# QCopterFC_MCU_Sch.net
KiCad netlist of a schematic drawn in Altium Designer
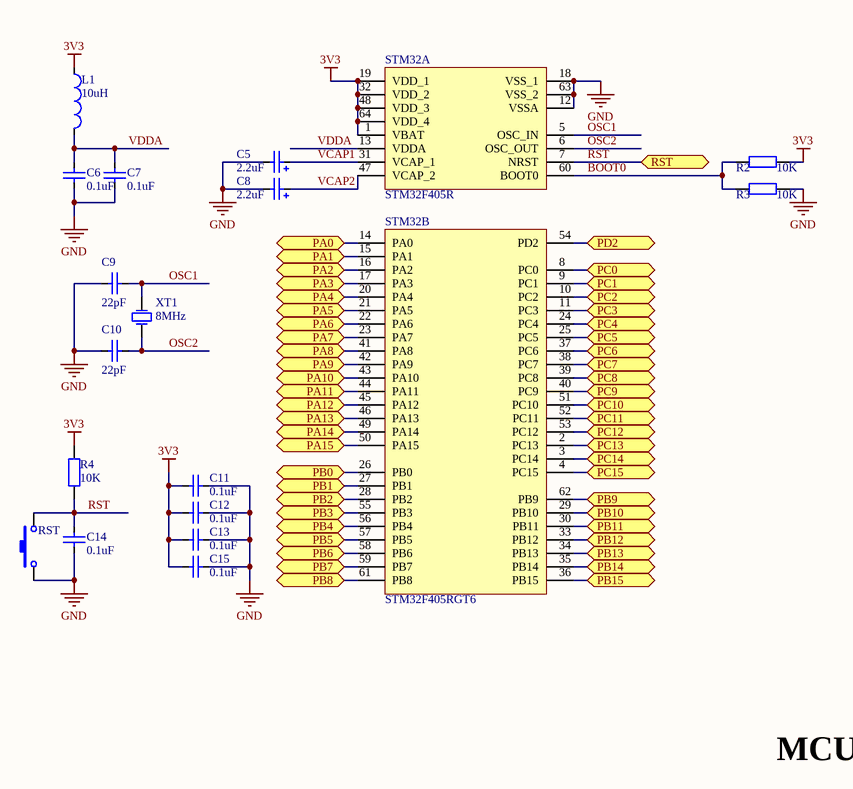
[diagram p0: QCopterFC_MCU_Sch.SchDoc]

(export (version "E")
  (design (tool "Eeschema 10.0.6"))
  (components
    (comp (ref "C5")
      (value "2.2uF")
      (footprint "PCB_Passive:CAP_TAN_P0805")
      (description "Capacitor")
      (fields (field (name "Comment") "Cap_Tan_0805"))
      (libsource (lib "SCH_Passive") (part "Cap_Tan_0805"))
    )
    (comp (ref "C6")
      (value "0.1uF")
      (footprint "PCB_Passive:CAP_0603")
      (description "Capacitor")
      (fields (field (name "Comment") "Cap_0603"))
      (libsource (lib "SCH_Passive") (part "Cap_0603"))
    )
    (comp (ref "C7")
      (value "0.1uF")
      (footprint "PCB_Passive:CAP_0603")
      (description "Capacitor")
      (fields (field (name "Comment") "Cap_0603"))
      (libsource (lib "SCH_Passive") (part "Cap_0603"))
    )
    (comp (ref "C8")
      (value "2.2uF")
      (footprint "PCB_Passive:CAP_TAN_P0805")
      (description "Capacitor")
      (fields (field (name "Comment") "Cap_Tan_0805"))
      (libsource (lib "SCH_Passive") (part "Cap_Tan_0805"))
    )
    (comp (ref "C9")
      (value "22pF")
      (footprint "PCB_Passive:CAP_0603")
      (description "Capacitor")
      (fields (field (name "Comment") "Cap_0603"))
      (libsource (lib "SCH_Passive") (part "Cap_0603"))
    )
    (comp (ref "C10")
      (value "22pF")
      (footprint "PCB_Passive:CAP_0603")
      (description "Capacitor")
      (fields (field (name "Comment") "Cap_0603"))
      (libsource (lib "SCH_Passive") (part "Cap_0603"))
    )
    (comp (ref "C11")
      (value "0.1uF")
      (footprint "PCB_Passive:CAP_0603")
      (description "Capacitor")
      (fields (field (name "Comment") "Cap_0603"))
      (libsource (lib "SCH_Passive") (part "Cap_0603"))
    )
    (comp (ref "C12")
      (value "0.1uF")
      (footprint "PCB_Passive:CAP_0603")
      (description "Capacitor")
      (fields (field (name "Comment") "Cap_0603"))
      (libsource (lib "SCH_Passive") (part "Cap_0603"))
    )
    (comp (ref "C13")
      (value "0.1uF")
      (footprint "PCB_Passive:CAP_0603")
      (description "Capacitor")
      (fields (field (name "Comment") "Cap_0603"))
      (libsource (lib "SCH_Passive") (part "Cap_0603"))
    )
    (comp (ref "C14")
      (value "0.1uF")
      (footprint "PCB_Passive:CAP_0603")
      (description "Capacitor")
      (fields (field (name "Comment") "Cap_0603"))
      (libsource (lib "SCH_Passive") (part "Cap_0603"))
    )
    (comp (ref "C15")
      (value "0.1uF")
      (footprint "PCB_Passive:CAP_0603")
      (description "Capacitor")
      (fields (field (name "Comment") "Cap_0603"))
      (libsource (lib "SCH_Passive") (part "Cap_0603"))
    )
    (comp (ref "L1")
      (value "10uH")
      (footprint "PCB_Passive:IND_0603")
      (description "Inductor")
      (fields (field (name "Comment") "Ind_0603"))
      (libsource (lib "SCH_Passive") (part "Ind_0603"))
    )
    (comp (ref "R2")
      (value "10K")
      (footprint "PCB_Passive:RES_0603")
      (description "Resistor")
      (fields (field (name "Comment") "Res_0603"))
      (libsource (lib "SCH_Passive") (part "Res_0603"))
    )
    (comp (ref "R3")
      (value "10K")
      (footprint "PCB_Passive:RES_0603")
      (description "Resistor")
      (fields (field (name "Comment") "Res_0603"))
      (libsource (lib "SCH_Passive") (part "Res_0603"))
    )
    (comp (ref "R4")
      (value "10K")
      (footprint "PCB_Passive:RES_0603")
      (description "Resistor")
      (fields (field (name "Comment") "Res_0603"))
      (libsource (lib "") (part "Res_0603_1"))
    )
    (comp (ref "RST")
      (value "SW-PB_1")
      (footprint "PCB_Switch:BT_90_T")
      (description "Switch")
      (fields (field (name "PUBLISHER") "Altium Limited"))
      (libsource (lib "SCH_Switch") (part "SW-PB_1"))
    )
    (comp (ref "STM32")
      (value "STM32F405R")
      (footprint "PCB_IC:STM32F_64")
      (description "MCU")
      (libsource (lib "") (part "STM32F405R_1"))
    )
    (comp (ref "XT1")
      (value "8MHz")
      (footprint "PCB_Oscillator:XTAL_5032")
      (description "Crystal Oscillator")
      (fields (field (name "Comment") "XTAL_5032") (field (name "PUBLISHER") "Altium Limited"))
      (libsource (lib "SCH_Oscillator") (part "XTAL_5032"))
    )
  )
  (nets
    (net (code "1") (name "/BOOT0") (class "Default")
      (node (ref "R2") (pin "1") (pinfunction "1_1") (pintype "passive"))
      (node (ref "R3") (pin "1") (pinfunction "1_1") (pintype "passive"))
      (node (ref "STM32") (pin "60") (pinfunction "BOOT0_60") (pintype "passive"))
    )
    (net (code "2") (name "/OSC1") (class "Default")
      (node (ref "C9") (pin "2") (pinfunction "2_2") (pintype "passive"))
      (node (ref "STM32") (pin "5") (pinfunction "OSC_IN_5") (pintype "passive"))
      (node (ref "XT1") (pin "2") (pinfunction "OSC2_2") (pintype "passive"))
    )
    (net (code "3") (name "/OSC2") (class "Default")
      (node (ref "C10") (pin "2") (pinfunction "2_2") (pintype "passive"))
      (node (ref "STM32") (pin "6") (pinfunction "OSC_OUT_6") (pintype "passive"))
      (node (ref "XT1") (pin "1") (pinfunction "OSC1_1") (pintype "passive"))
    )
    (net (code "4") (name "/PA0") (class "Default")
      (node (ref "STM32") (pin "14") (pinfunction "PA0_14") (pintype "passive"))
    )
    (net (code "5") (name "/PA1") (class "Default")
      (node (ref "STM32") (pin "15") (pinfunction "PA1_15") (pintype "passive"))
    )
    (net (code "6") (name "/PA2") (class "Default")
      (node (ref "STM32") (pin "16") (pinfunction "PA2_16") (pintype "passive"))
    )
    (net (code "7") (name "/PA3") (class "Default")
      (node (ref "STM32") (pin "17") (pinfunction "PA3_17") (pintype "passive"))
    )
    (net (code "8") (name "/PA4") (class "Default")
      (node (ref "STM32") (pin "20") (pinfunction "PA4_20") (pintype "passive"))
    )
    (net (code "9") (name "/PA5") (class "Default")
      (node (ref "STM32") (pin "21") (pinfunction "PA5_21") (pintype "passive"))
    )
    (net (code "10") (name "/PA6") (class "Default")
      (node (ref "STM32") (pin "22") (pinfunction "PA6_22") (pintype "passive"))
    )
    (net (code "11") (name "/PA7") (class "Default")
      (node (ref "STM32") (pin "23") (pinfunction "PA7_23") (pintype "passive"))
    )
    (net (code "12") (name "/PA8") (class "Default")
      (node (ref "STM32") (pin "41") (pinfunction "PA8_41") (pintype "passive"))
    )
    (net (code "13") (name "/PA9") (class "Default")
      (node (ref "STM32") (pin "42") (pinfunction "PA9_42") (pintype "passive"))
    )
    (net (code "14") (name "/PA10") (class "Default")
      (node (ref "STM32") (pin "43") (pinfunction "PA10_43") (pintype "passive"))
    )
    (net (code "15") (name "/PA11") (class "Default")
      (node (ref "STM32") (pin "44") (pinfunction "PA11_44") (pintype "passive"))
    )
    (net (code "16") (name "/PA12") (class "Default")
      (node (ref "STM32") (pin "45") (pinfunction "PA12_45") (pintype "passive"))
    )
    (net (code "17") (name "/PA13") (class "Default")
      (node (ref "STM32") (pin "46") (pinfunction "PA13_46") (pintype "passive"))
    )
    (net (code "18") (name "/PA14") (class "Default")
      (node (ref "STM32") (pin "49") (pinfunction "PA14_49") (pintype "passive"))
    )
    (net (code "19") (name "/PA15") (class "Default")
      (node (ref "STM32") (pin "50") (pinfunction "PA15_50") (pintype "passive"))
    )
    (net (code "20") (name "/PB0") (class "Default")
      (node (ref "STM32") (pin "26") (pinfunction "PB0_26") (pintype "passive"))
    )
    (net (code "21") (name "/PB1") (class "Default")
      (node (ref "STM32") (pin "27") (pinfunction "PB1_27") (pintype "passive"))
    )
    (net (code "22") (name "/PB2") (class "Default")
      (node (ref "STM32") (pin "28") (pinfunction "PB2_28") (pintype "passive"))
    )
    (net (code "23") (name "/PB3") (class "Default")
      (node (ref "STM32") (pin "55") (pinfunction "PB3_55") (pintype "passive"))
    )
    (net (code "24") (name "/PB4") (class "Default")
      (node (ref "STM32") (pin "56") (pinfunction "PB4_56") (pintype "passive"))
    )
    (net (code "25") (name "/PB5") (class "Default")
      (node (ref "STM32") (pin "57") (pinfunction "PB5_57") (pintype "passive"))
    )
    (net (code "26") (name "/PB6") (class "Default")
      (node (ref "STM32") (pin "58") (pinfunction "PB6_58") (pintype "passive"))
    )
    (net (code "27") (name "/PB7") (class "Default")
      (node (ref "STM32") (pin "59") (pinfunction "PB7_59") (pintype "passive"))
    )
    (net (code "28") (name "/PB8") (class "Default")
      (node (ref "STM32") (pin "61") (pinfunction "PB8_61") (pintype "passive"))
    )
    (net (code "29") (name "/PB9") (class "Default")
      (node (ref "STM32") (pin "62") (pinfunction "PB9_62") (pintype "passive"))
    )
    (net (code "30") (name "/PB10") (class "Default")
      (node (ref "STM32") (pin "29") (pinfunction "PB10_29") (pintype "passive"))
    )
    (net (code "31") (name "/PB11") (class "Default")
      (node (ref "STM32") (pin "30") (pinfunction "PB11_30") (pintype "passive"))
    )
    (net (code "32") (name "/PB12") (class "Default")
      (node (ref "STM32") (pin "33") (pinfunction "PB12_33") (pintype "passive"))
    )
    (net (code "33") (name "/PB13") (class "Default")
      (node (ref "STM32") (pin "34") (pinfunction "PB13_34") (pintype "passive"))
    )
    (net (code "34") (name "/PB14") (class "Default")
      (node (ref "STM32") (pin "35") (pinfunction "PB14_35") (pintype "passive"))
    )
    (net (code "35") (name "/PB15") (class "Default")
      (node (ref "STM32") (pin "36") (pinfunction "PB15_36") (pintype "passive"))
    )
    (net (code "36") (name "/PC0") (class "Default")
      (node (ref "STM32") (pin "8") (pinfunction "PC0_8") (pintype "passive"))
    )
    (net (code "37") (name "/PC1") (class "Default")
      (node (ref "STM32") (pin "9") (pinfunction "PC1_9") (pintype "passive"))
    )
    (net (code "38") (name "/PC2") (class "Default")
      (node (ref "STM32") (pin "10") (pinfunction "PC2_10") (pintype "passive"))
    )
    (net (code "39") (name "/PC3") (class "Default")
      (node (ref "STM32") (pin "11") (pinfunction "PC3_11") (pintype "passive"))
    )
    (net (code "40") (name "/PC4") (class "Default")
      (node (ref "STM32") (pin "24") (pinfunction "PC4_24") (pintype "passive"))
    )
    (net (code "41") (name "/PC5") (class "Default")
      (node (ref "STM32") (pin "25") (pinfunction "PC5_25") (pintype "passive"))
    )
    (net (code "42") (name "/PC6") (class "Default")
      (node (ref "STM32") (pin "37") (pinfunction "PC6_37") (pintype "passive"))
    )
    (net (code "43") (name "/PC7") (class "Default")
      (node (ref "STM32") (pin "38") (pinfunction "PC7_38") (pintype "passive"))
    )
    (net (code "44") (name "/PC8") (class "Default")
      (node (ref "STM32") (pin "39") (pinfunction "PC8_39") (pintype "passive"))
    )
    (net (code "45") (name "/PC9") (class "Default")
      (node (ref "STM32") (pin "40") (pinfunction "PC9_40") (pintype "passive"))
    )
    (net (code "46") (name "/PC10") (class "Default")
      (node (ref "STM32") (pin "51") (pinfunction "PC10_51") (pintype "passive"))
    )
    (net (code "47") (name "/PC11") (class "Default")
      (node (ref "STM32") (pin "52") (pinfunction "PC11_52") (pintype "passive"))
    )
    (net (code "48") (name "/PC12") (class "Default")
      (node (ref "STM32") (pin "53") (pinfunction "PC12_53") (pintype "passive"))
    )
    (net (code "49") (name "/PC13") (class "Default")
      (node (ref "STM32") (pin "2") (pinfunction "PC13_2") (pintype "passive"))
    )
    (net (code "50") (name "/PC14") (class "Default")
      (node (ref "STM32") (pin "3") (pinfunction "PC14_3") (pintype "passive"))
    )
    (net (code "51") (name "/PC15") (class "Default")
      (node (ref "STM32") (pin "4") (pinfunction "PC15_4") (pintype "passive"))
    )
    (net (code "52") (name "/PD2") (class "Default")
      (node (ref "STM32") (pin "54") (pinfunction "PD2_54") (pintype "passive"))
    )
    (net (code "53") (name "/RST") (class "Default")
      (node (ref "C14") (pin "1") (pinfunction "1_1") (pintype "passive"))
      (node (ref "R4") (pin "2") (pinfunction "2_2") (pintype "passive"))
      (node (ref "RST") (pin "2") (pinfunction "2_2") (pintype "passive"))
      (node (ref "STM32") (pin "7") (pinfunction "NRST_7") (pintype "passive"))
    )
    (net (code "54") (name "/VCAP1") (class "Default")
      (node (ref "C5") (pin "1") (pinfunction "1_1") (pintype "passive"))
      (node (ref "STM32") (pin "31") (pinfunction "VCAP_1_31") (pintype "passive"))
    )
    (net (code "55") (name "/VCAP2") (class "Default")
      (node (ref "C8") (pin "1") (pinfunction "1_1") (pintype "passive"))
      (node (ref "STM32") (pin "47") (pinfunction "VCAP_2_47") (pintype "passive"))
    )
    (net (code "56") (name "/VDDA") (class "Default")
      (node (ref "C6") (pin "1") (pinfunction "1_1") (pintype "passive"))
      (node (ref "C7") (pin "1") (pinfunction "1_1") (pintype "passive"))
      (node (ref "L1") (pin "2") (pinfunction "2_2") (pintype "passive"))
      (node (ref "STM32") (pin "13") (pinfunction "VDDA_13") (pintype "passive"))
    )
    (net (code "57") (name "3V3") (class "Default")
      (node (ref "C11") (pin "2") (pinfunction "2_2") (pintype "passive"))
      (node (ref "C12") (pin "2") (pinfunction "2_2") (pintype "passive"))
      (node (ref "C13") (pin "2") (pinfunction "2_2") (pintype "passive"))
      (node (ref "C15") (pin "2") (pinfunction "2_2") (pintype "passive"))
      (node (ref "L1") (pin "1") (pinfunction "1_1") (pintype "passive"))
      (node (ref "R2") (pin "2") (pinfunction "2_2") (pintype "passive"))
      (node (ref "R4") (pin "1") (pinfunction "1_1") (pintype "passive"))
      (node (ref "STM32") (pin "1") (pinfunction "VBAT_1") (pintype "passive"))
      (node (ref "STM32") (pin "19") (pinfunction "VDD_1_19") (pintype "passive"))
      (node (ref "STM32") (pin "32") (pinfunction "VDD_2_32") (pintype "passive"))
      (node (ref "STM32") (pin "48") (pinfunction "VDD_3_48") (pintype "passive"))
      (node (ref "STM32") (pin "64") (pinfunction "VDD_4_64") (pintype "passive"))
    )
    (net (code "58") (name "GND") (class "Default")
      (node (ref "C10") (pin "1") (pinfunction "1_1") (pintype "passive"))
      (node (ref "C11") (pin "1") (pinfunction "1_1") (pintype "passive"))
      (node (ref "C12") (pin "1") (pinfunction "1_1") (pintype "passive"))
      (node (ref "C13") (pin "1") (pinfunction "1_1") (pintype "passive"))
      (node (ref "C14") (pin "2") (pinfunction "2_2") (pintype "passive"))
      (node (ref "C15") (pin "1") (pinfunction "1_1") (pintype "passive"))
      (node (ref "C5") (pin "2") (pinfunction "2_2") (pintype "passive"))
      (node (ref "C6") (pin "2") (pinfunction "2_2") (pintype "passive"))
      (node (ref "C7") (pin "2") (pinfunction "2_2") (pintype "passive"))
      (node (ref "C8") (pin "2") (pinfunction "2_2") (pintype "passive"))
      (node (ref "C9") (pin "1") (pinfunction "1_1") (pintype "passive"))
      (node (ref "R3") (pin "2") (pinfunction "2_2") (pintype "passive"))
      (node (ref "RST") (pin "1") (pinfunction "1_1") (pintype "passive"))
      (node (ref "STM32") (pin "12") (pinfunction "VSSA_12") (pintype "passive"))
      (node (ref "STM32") (pin "18") (pinfunction "VSS_1_18") (pintype "passive"))
      (node (ref "STM32") (pin "63") (pinfunction "VSS_2_63") (pintype "passive"))
    )
  )
)
